# Quad_Board.net
KiCad netlist of a schematic drawn in EAGLE
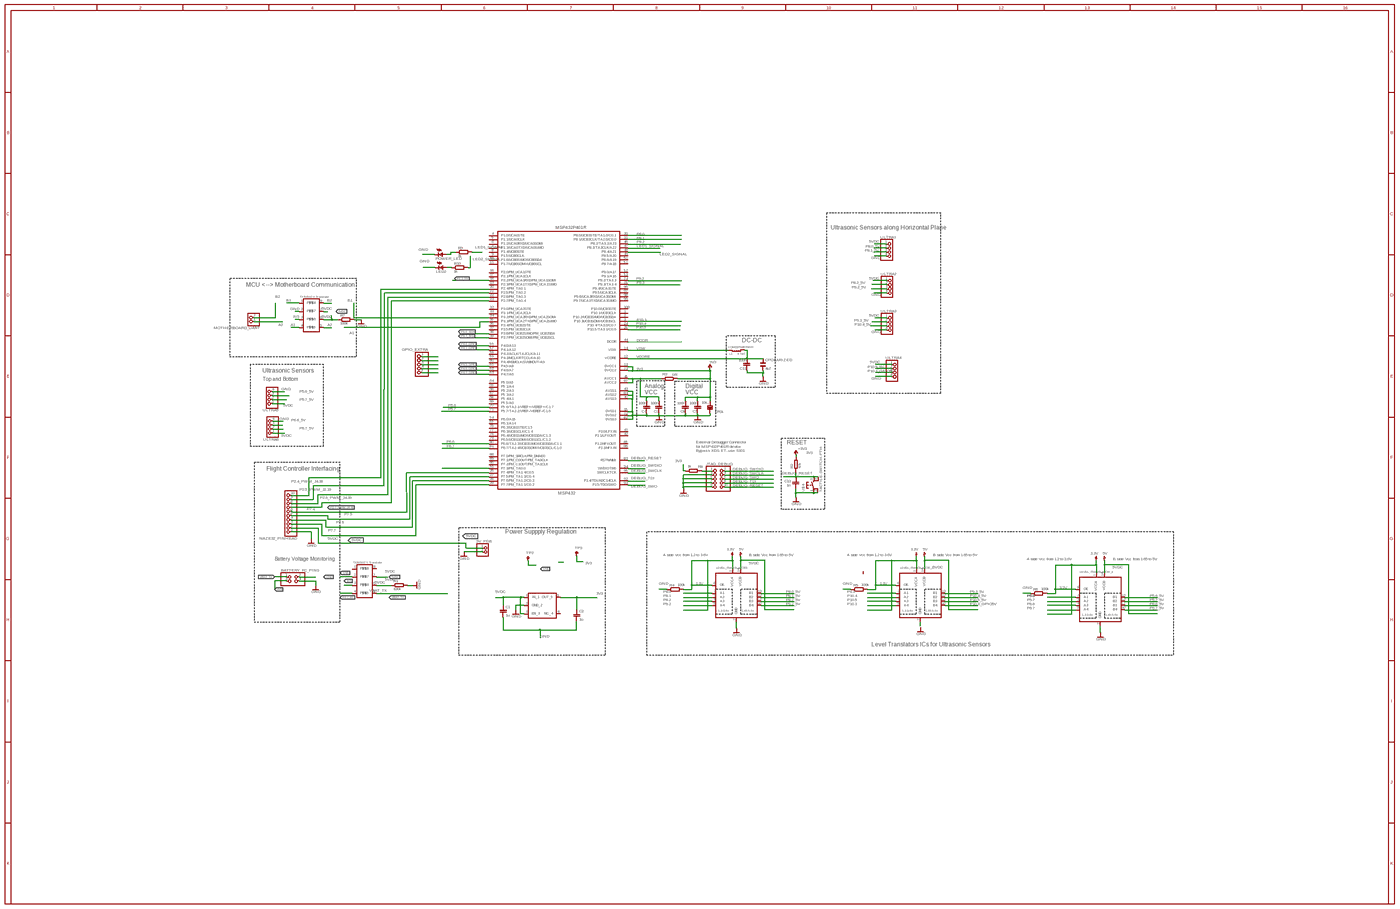
[diagram p0: schematic, sheet 1, overview]
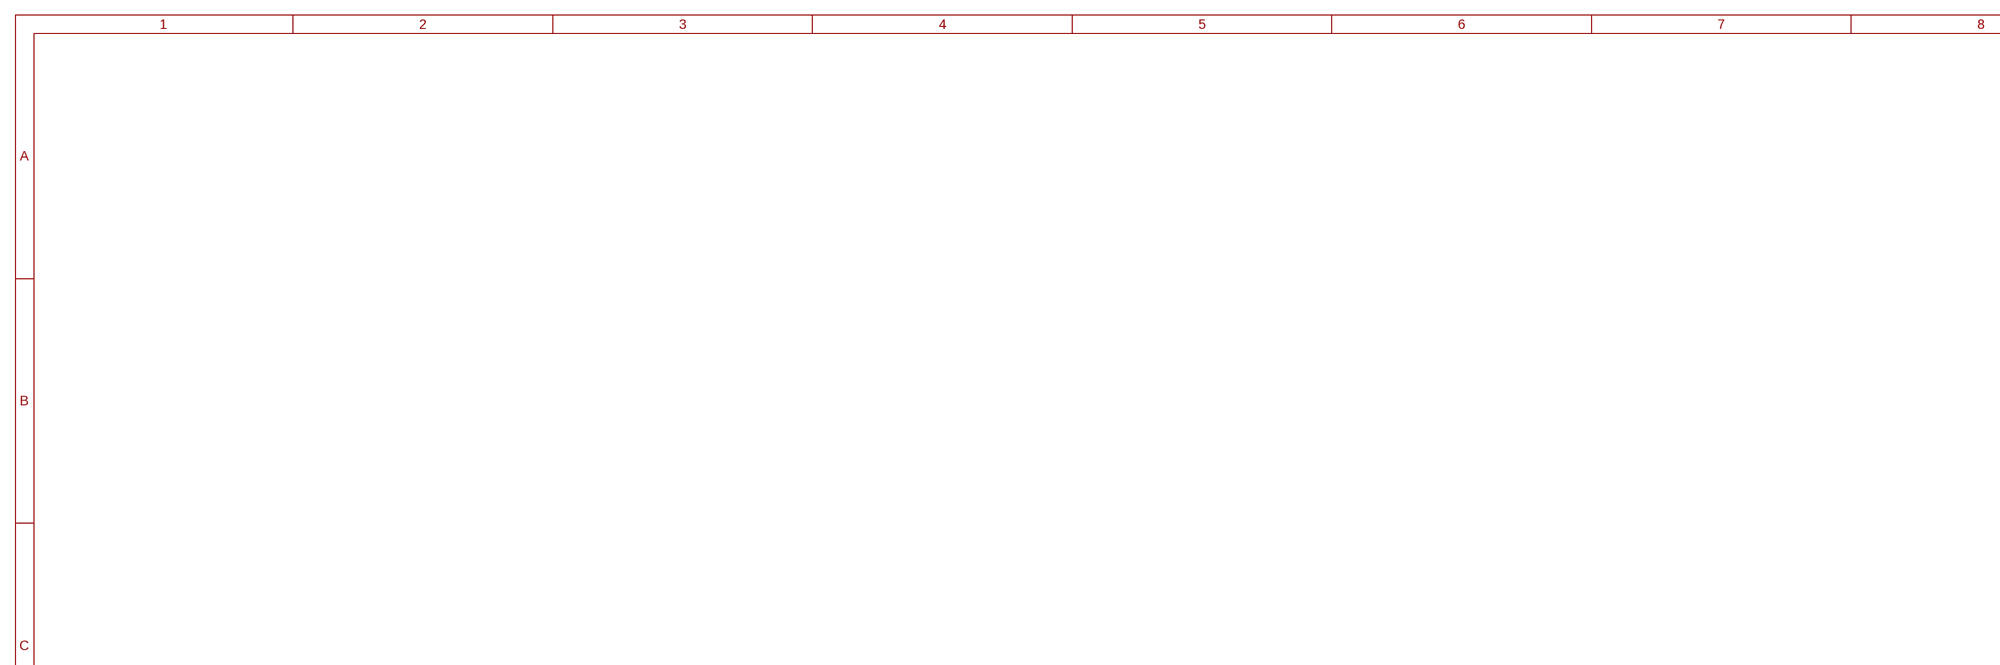
[diagram p1: schematic, sheet 1, part 1 of 4]
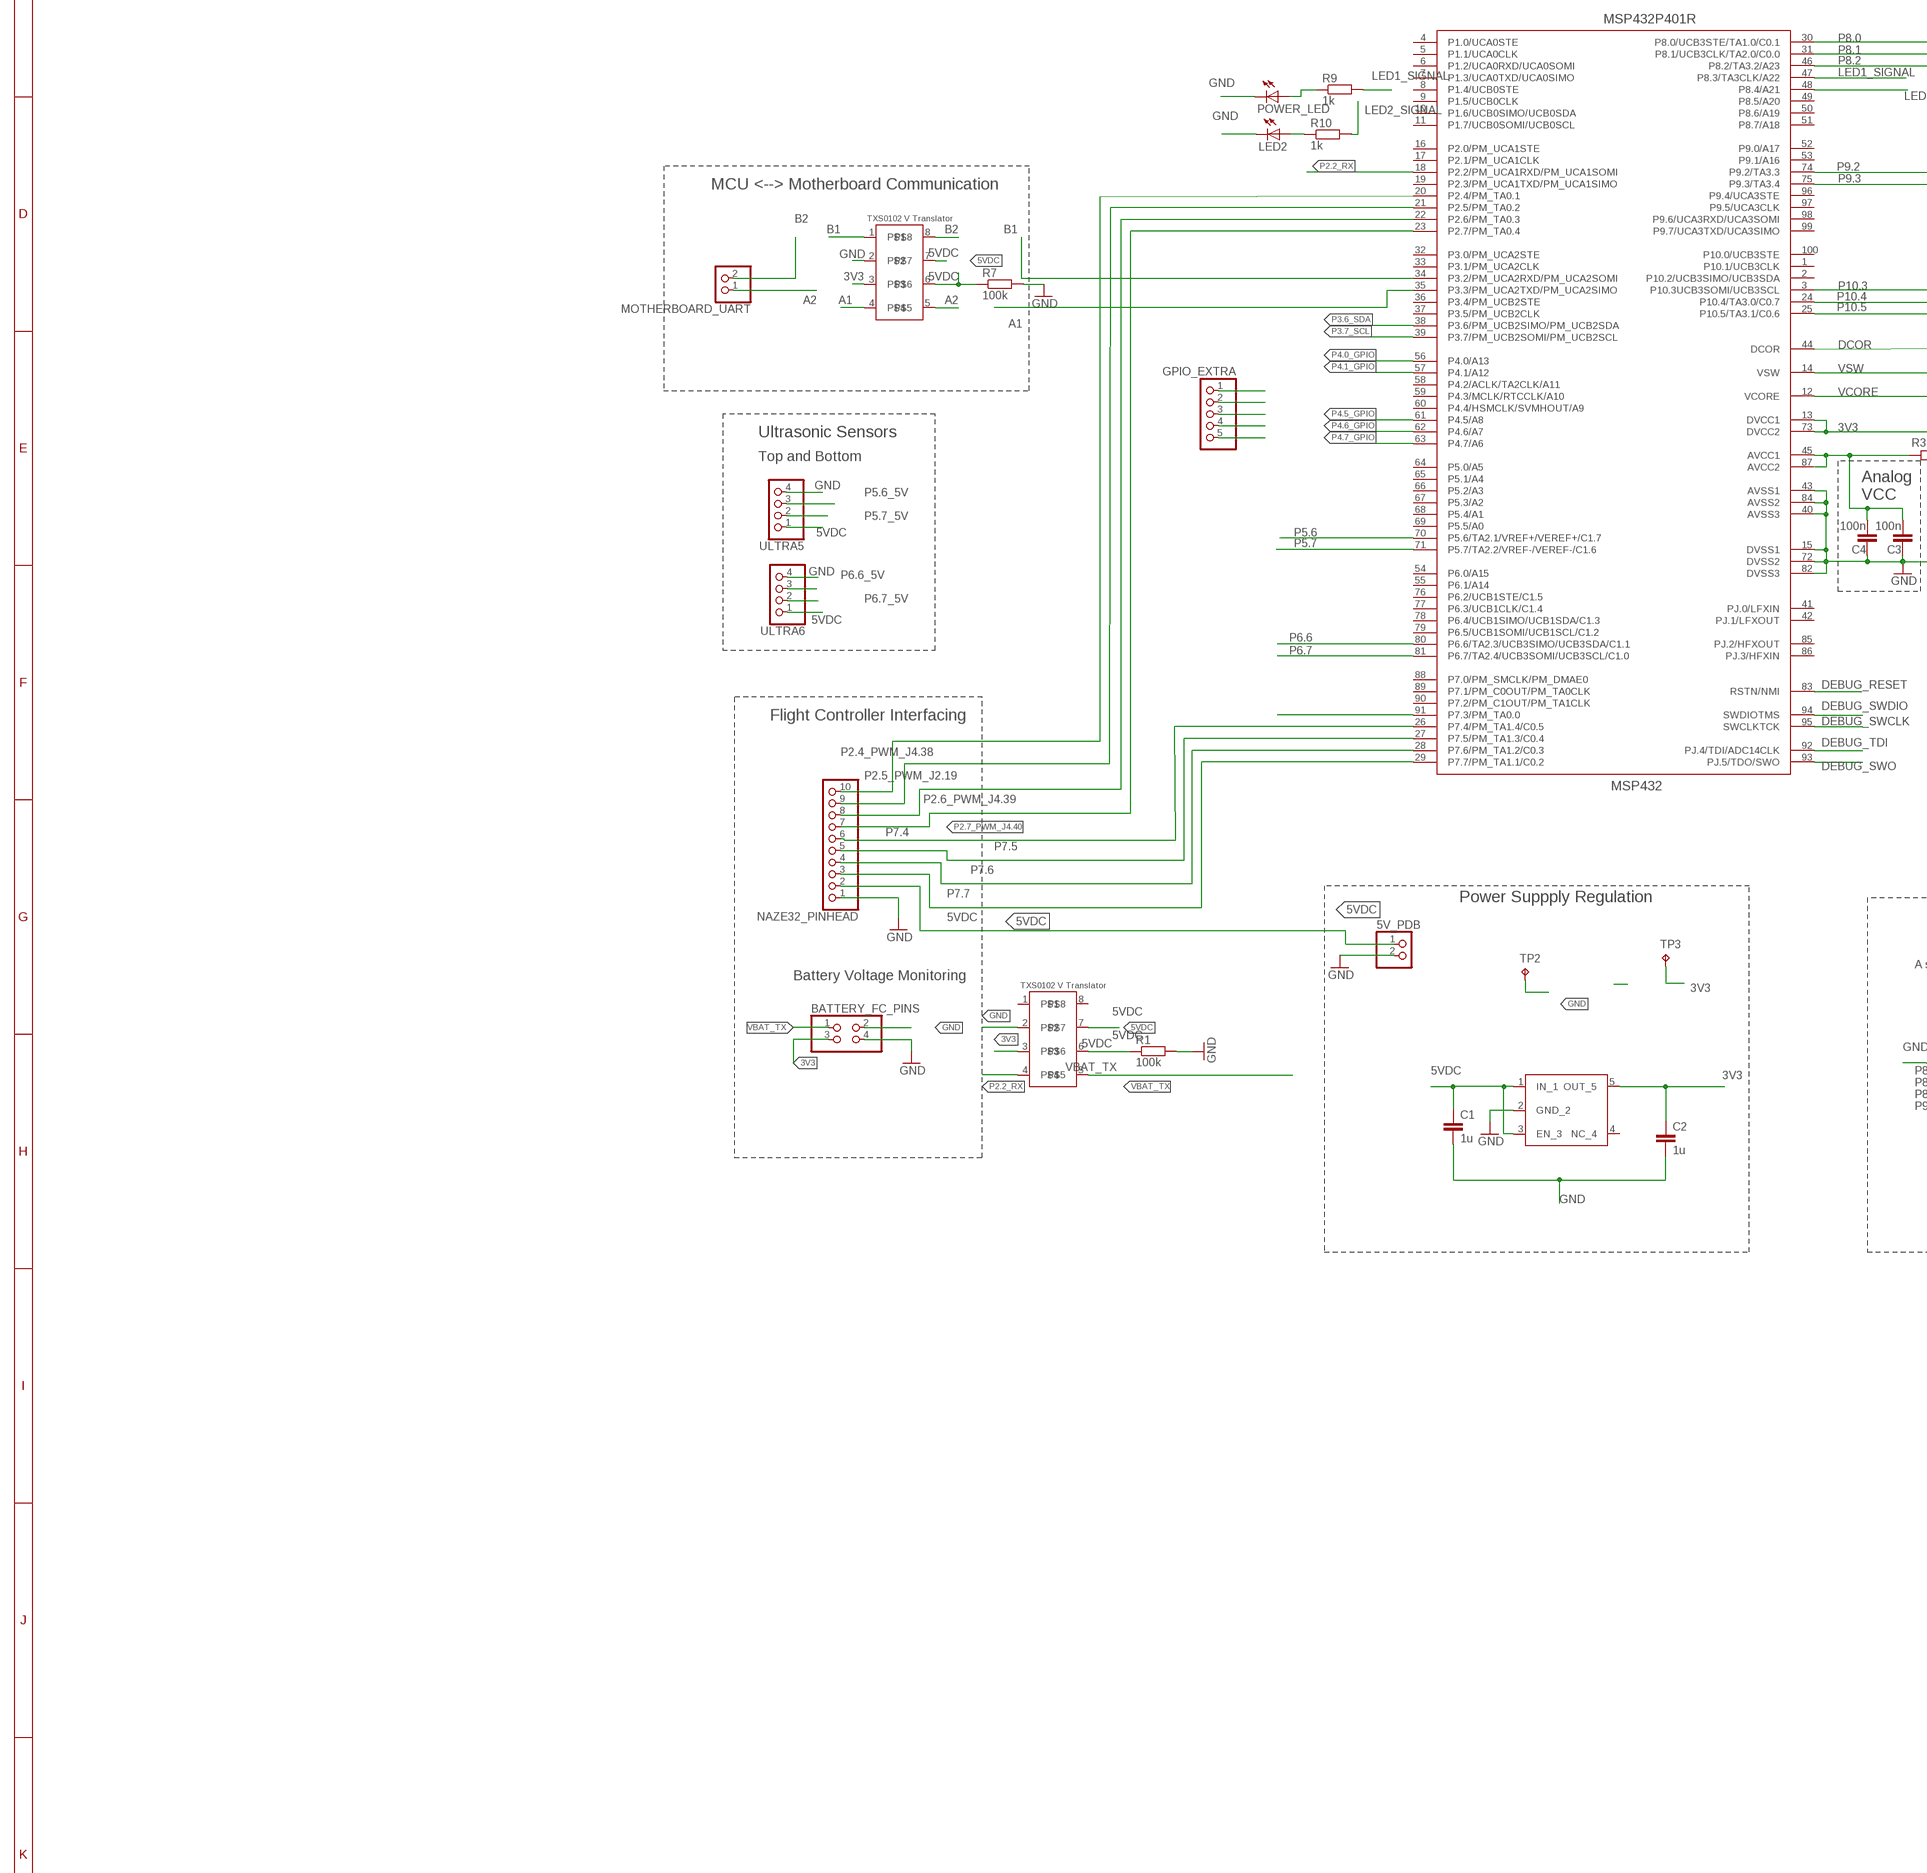
[diagram p2: schematic, sheet 1, part 2 of 4]
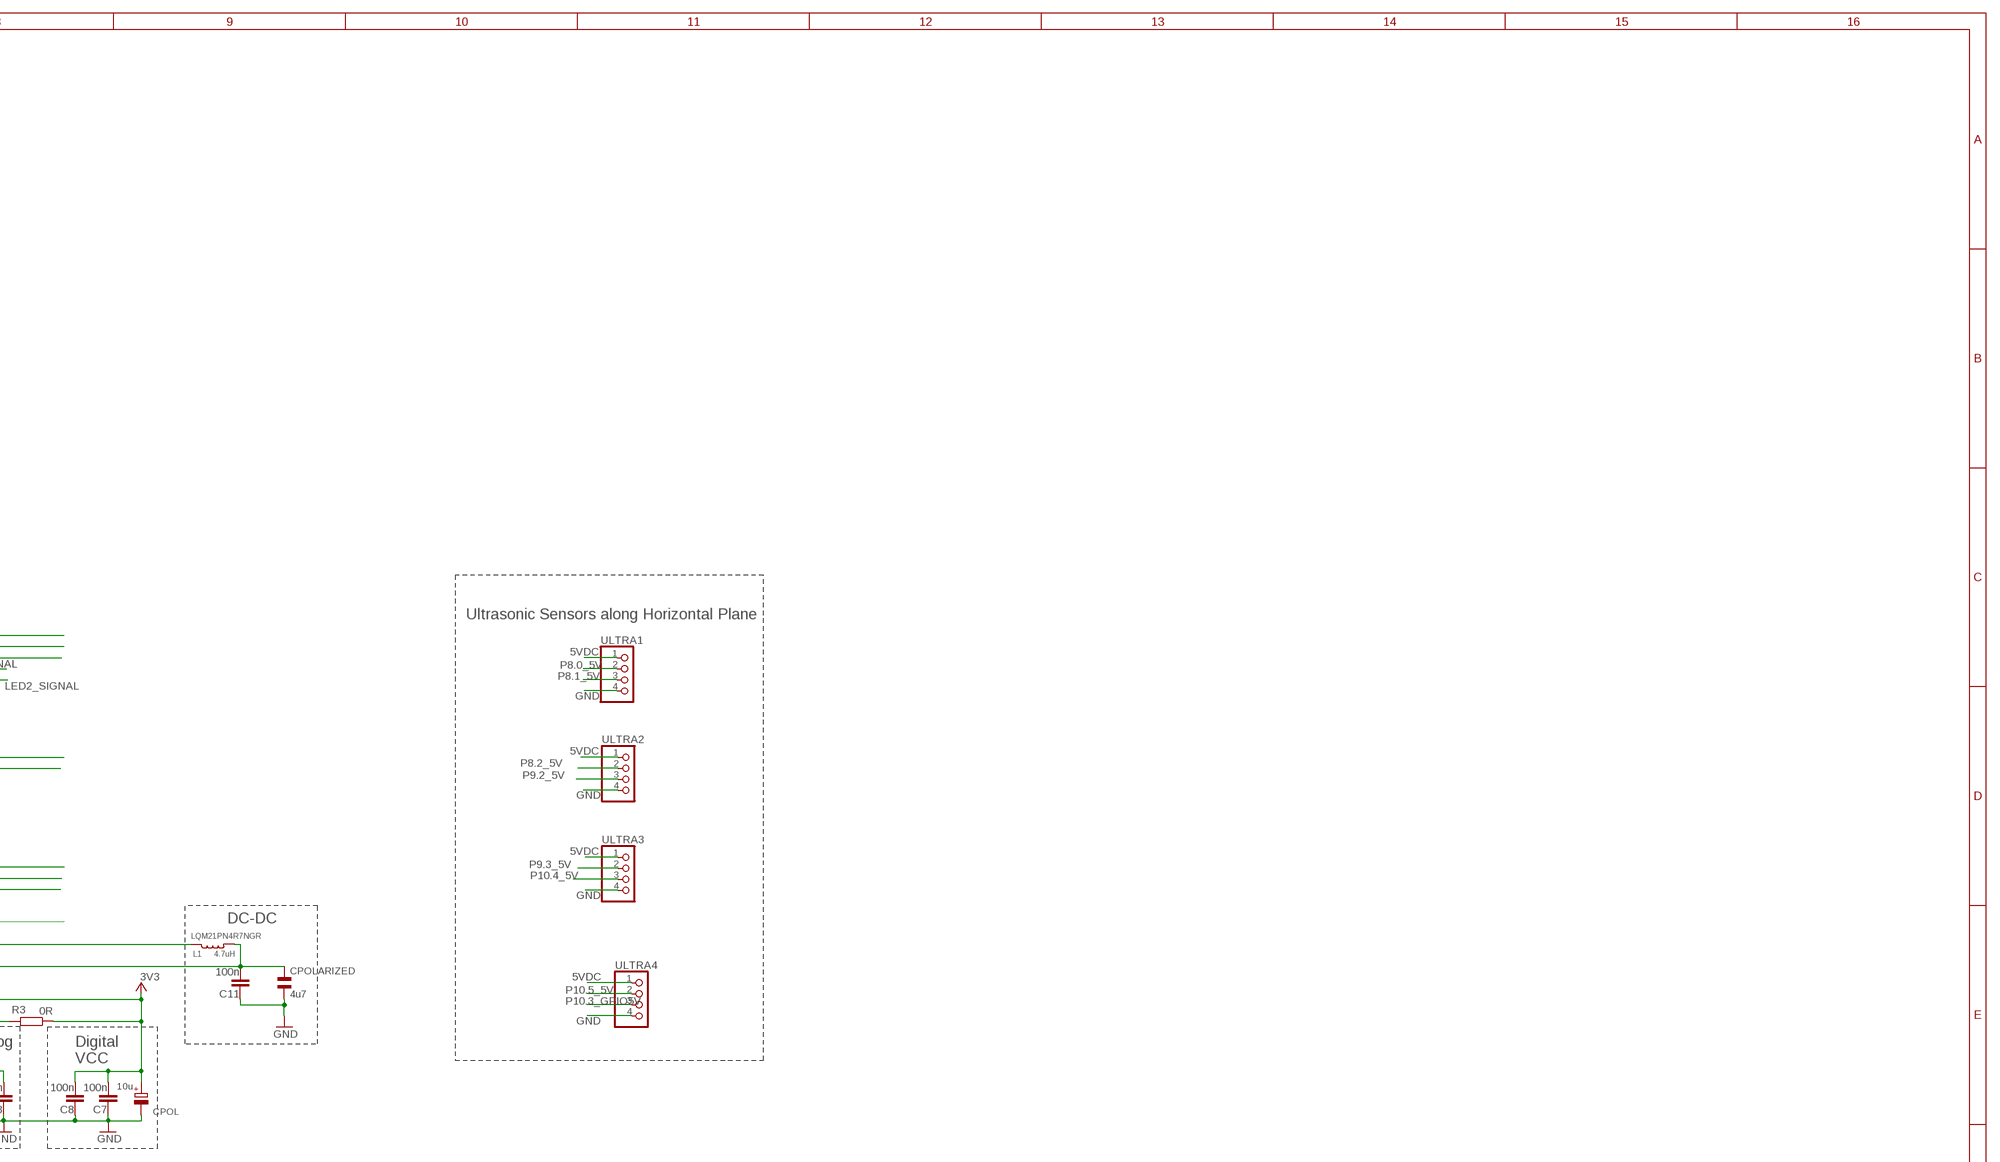
[diagram p3: schematic, sheet 1, part 3 of 4]
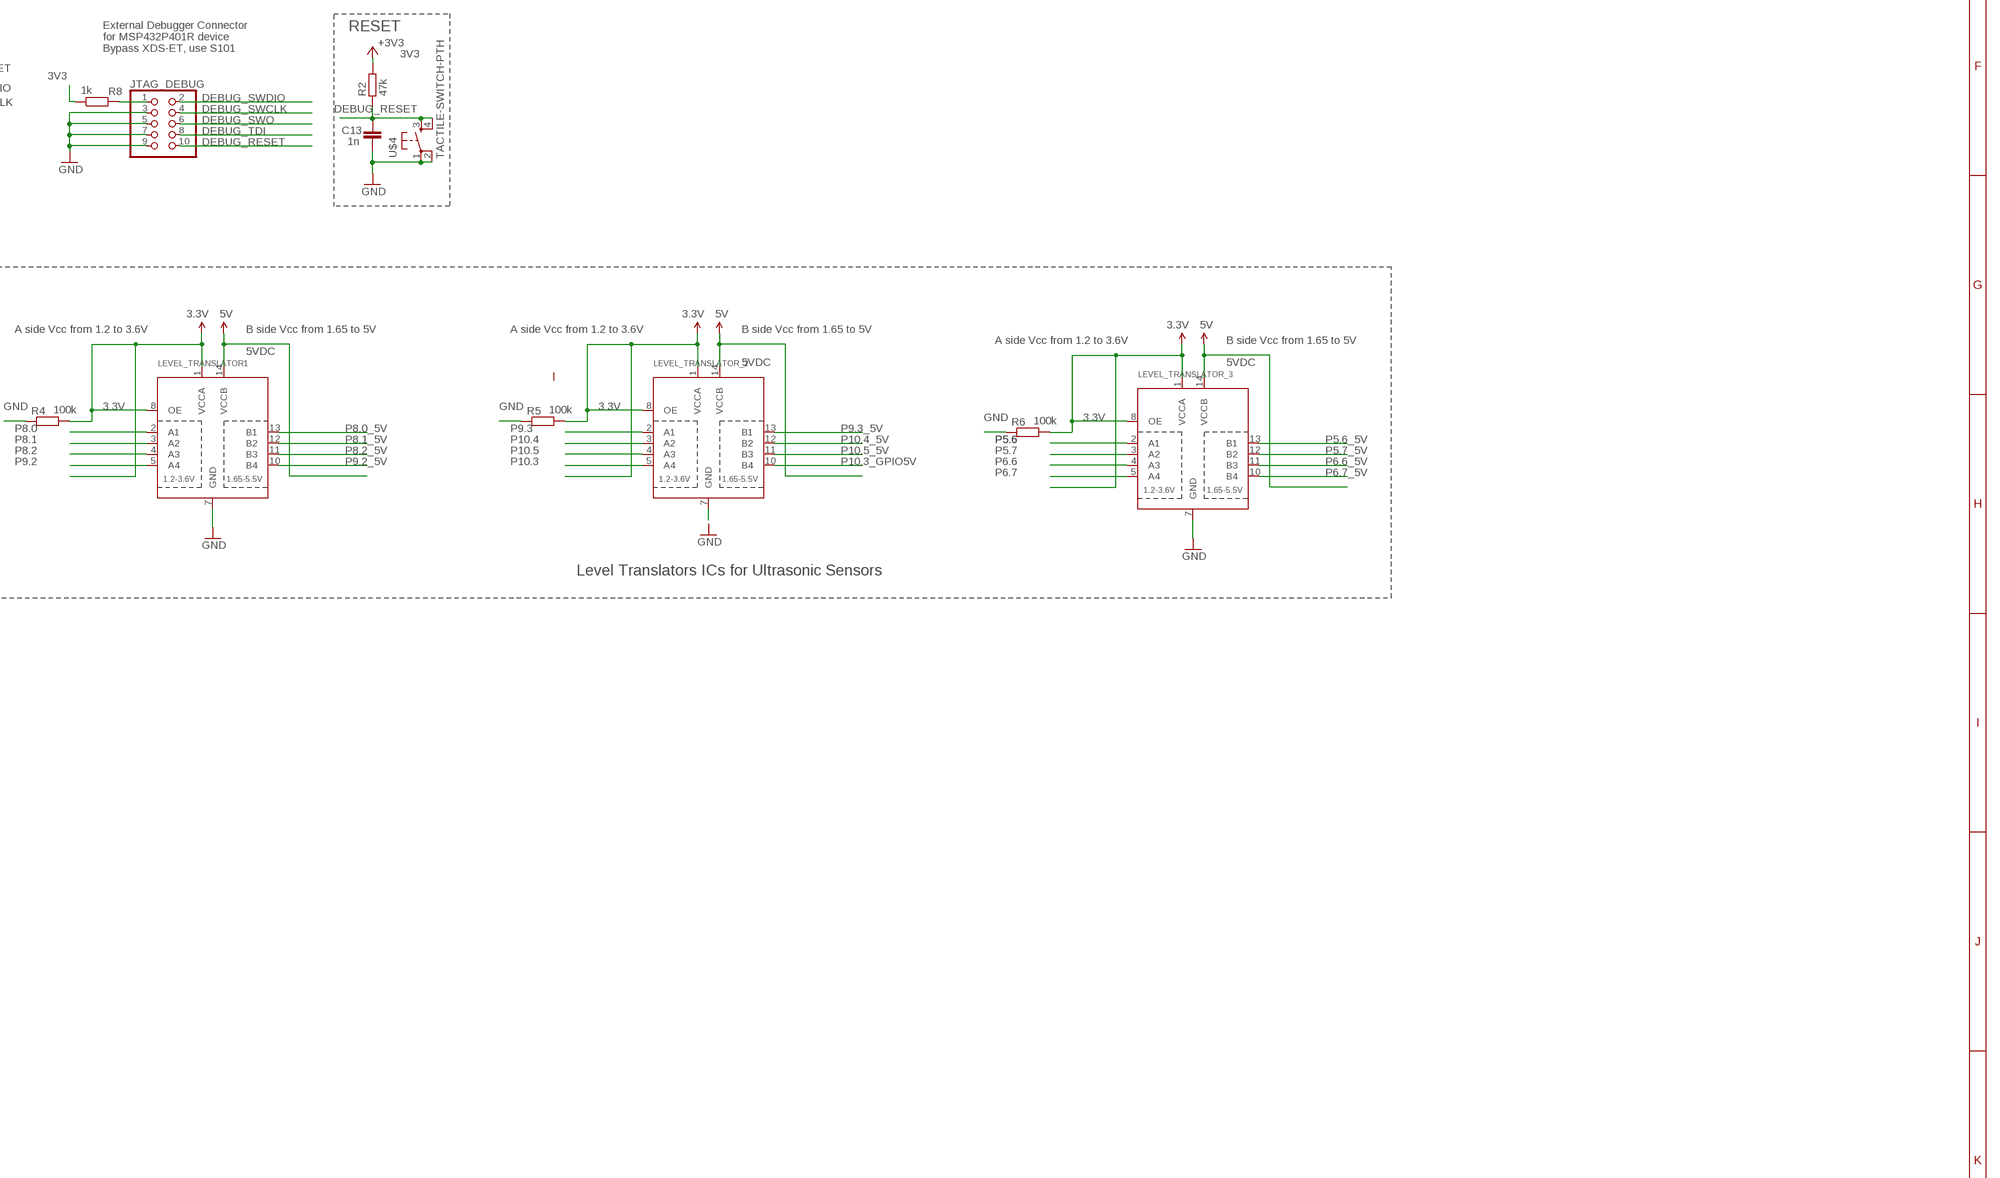
[diagram p4: schematic, sheet 1, part 4 of 4]

(export (version "E")
  (design (tool "Eeschema 10.0.6"))
  (components
    (comp (ref "5V_PDB")
      (value "PINHD-1X2")
      (footprint "eagle-import:1X02")
      (libsource (lib "eagle-import") (part "PINHD-1X2"))
    )
    (comp (ref "BATTERY_FC_PINS")
      (value "PINHD-2X2")
      (footprint "eagle-import:2X02")
      (libsource (lib "eagle-import") (part "PINHD-2X2"))
    )
    (comp (ref "C1")
      (value "1u")
      (footprint "eagle-import:C0805")
      (libsource (lib "eagle-import") (part "C-EUC0805"))
    )
    (comp (ref "C2")
      (value "1u")
      (footprint "eagle-import:C0805")
      (libsource (lib "eagle-import") (part "C-EUC0805"))
    )
    (comp (ref "C3")
      (value "100n")
      (footprint "eagle-import:C0805")
      (libsource (lib "eagle-import") (part "C-EUC0805"))
    )
    (comp (ref "C4")
      (value "100n")
      (footprint "eagle-import:C0805")
      (libsource (lib "eagle-import") (part "C-EUC0805"))
    )
    (comp (ref "C7")
      (value "100n")
      (footprint "eagle-import:C0805")
      (libsource (lib "eagle-import") (part "C-EUC0805"))
    )
    (comp (ref "C8")
      (value "100n")
      (footprint "eagle-import:C0805")
      (libsource (lib "eagle-import") (part "C-EUC0805"))
    )
    (comp (ref "C11")
      (value "100n")
      (footprint "eagle-import:C0805")
      (libsource (lib "eagle-import") (part "C-EUC0805"))
    )
    (comp (ref "C13")
      (value "1n")
      (footprint "eagle-import:C0805")
      (libsource (lib "eagle-import") (part "C-EUC0805"))
    )
    (comp (ref "CPOL")
      (value "10u")
      (footprint "eagle-import:A_3216-18R")
      (libsource (lib "eagle-import") (part "CPOL-EUA/3216-18R"))
    )
    (comp (ref "CPOLARIZED")
      (value "4u7")
      (footprint "eagle-import:CSMD0805")
      (libsource (lib "eagle-import") (part "CSMD0805"))
    )
    (comp (ref "GPIO_EXTRA")
      (value "PINHD-1X5")
      (footprint "eagle-import:1X05")
      (libsource (lib "eagle-import") (part "PINHD-1X5"))
    )
    (comp (ref "JTAG_DEBUG")
      (value "PINHD-2X5")
      (footprint "eagle-import:2X05")
      (libsource (lib "eagle-import") (part "PINHD-2X5"))
    )
    (comp (ref "L1")
      (value "4.7uH")
      (footprint "eagle-import:0806")
      (libsource (lib "eagle-import") (part "LQM2MP_G0"))
    )
    (comp (ref "LED2")
      (value "LED_E")
      (footprint "eagle-import:LED_1206")
      (libsource (lib "eagle-import") (part "LED_E"))
    )
    (comp (ref "LEVEL_TRANSLATOR1")
      (value "TXB0104PWRSOIC14")
      (footprint "eagle-import:SO14")
      (libsource (lib "eagle-import") (part "TXB0104PWRSOIC14"))
    )
    (comp (ref "LEVEL_TRANSLATOR_2")
      (value "TXB0104PWRSOIC14")
      (footprint "eagle-import:SO14")
      (libsource (lib "eagle-import") (part "TXB0104PWRSOIC14"))
    )
    (comp (ref "LEVEL_TRANSLATOR_3")
      (value "TXB0104PWRSOIC14")
      (footprint "eagle-import:SO14")
      (libsource (lib "eagle-import") (part "TXB0104PWRSOIC14"))
    )
    (comp (ref "MOTHERBOARD_UART")
      (value "PINHD-1X2")
      (footprint "eagle-import:1X02")
      (libsource (lib "eagle-import") (part "PINHD-1X2"))
    )
    (comp (ref "MSP432P401R")
      (value "MSP432")
      (footprint "eagle-import:PZ100")
      (libsource (lib "eagle-import") (part "MSP432"))
    )
    (comp (ref "NAZE32_PINHEAD")
      (value "PINHD-1X10")
      (footprint "eagle-import:1X10")
      (libsource (lib "eagle-import") (part "PINHD-1X10"))
    )
    (comp (ref "POWER_LED")
      (value "LED_E")
      (footprint "eagle-import:LED_1206")
      (libsource (lib "eagle-import") (part "LED_E"))
    )
    (comp (ref "R1")
      (value "100k")
      (footprint "eagle-import:M1206")
      (libsource (lib "eagle-import") (part "resistor_R-EU_M1206"))
    )
    (comp (ref "R2")
      (value "47k")
      (footprint "eagle-import:R1206")
      (libsource (lib "eagle-import") (part "R-EU_R1206"))
    )
    (comp (ref "R3")
      (value "0R")
      (footprint "eagle-import:0402")
      (libsource (lib "eagle-import") (part "R-EU_RM0402"))
    )
    (comp (ref "R4")
      (value "100k")
      (footprint "eagle-import:M1206")
      (libsource (lib "eagle-import") (part "resistor_R-EU_M1206"))
    )
    (comp (ref "R5")
      (value "100k")
      (footprint "eagle-import:M1206")
      (libsource (lib "eagle-import") (part "resistor_R-EU_M1206"))
    )
    (comp (ref "R6")
      (value "100k")
      (footprint "eagle-import:M1206")
      (libsource (lib "eagle-import") (part "resistor_R-EU_M1206"))
    )
    (comp (ref "R7")
      (value "100k")
      (footprint "eagle-import:M1206")
      (libsource (lib "eagle-import") (part "resistor_R-EU_M1206"))
    )
    (comp (ref "R8")
      (value "1k")
      (footprint "eagle-import:R1206")
      (libsource (lib "eagle-import") (part "R-EU_R1206"))
    )
    (comp (ref "R9")
      (value "1k")
      (footprint "eagle-import:M0805")
      (libsource (lib "eagle-import") (part "resistor_R-EU_M0805"))
    )
    (comp (ref "R10")
      (value "1k")
      (footprint "eagle-import:M0805")
      (libsource (lib "eagle-import") (part "resistor_R-EU_M0805"))
    )
    (comp (ref "TP2")
      (value "TPB2,54")
      (footprint "eagle-import:B2,54")
      (libsource (lib "eagle-import") (part "TPB2,54"))
    )
    (comp (ref "TP3")
      (value "TPB2,54")
      (footprint "eagle-import:B2,54")
      (libsource (lib "eagle-import") (part "TPB2,54"))
    )
    (comp (ref "U$1")
      (value "TXS0102")
      (footprint "eagle-import:DCT_R-PDSO-G8")
      (libsource (lib "eagle-import") (part "TXS0102"))
    )
    (comp (ref "U$2")
      (value "TLV733P")
      (footprint "eagle-import:SOT23-5")
      (libsource (lib "eagle-import") (part "TLV733P"))
    )
    (comp (ref "U$3")
      (value "TXS0102")
      (footprint "eagle-import:DCT_R-PDSO-G8")
      (libsource (lib "eagle-import") (part "TXS0102"))
    )
    (comp (ref "U$4")
      (value "TACTILE-SWITCH-PTH")
      (footprint "eagle-import:TAC-SWITCH-PTH")
      (libsource (lib "eagle-import") (part "TACTILE-SWITCH-PTH"))
    )
    (comp (ref "ULTRA1")
      (value "PINHD-1X4")
      (footprint "eagle-import:1X04")
      (libsource (lib "eagle-import") (part "PINHD-1X4"))
    )
    (comp (ref "ULTRA2")
      (value "PINHD-1X4")
      (footprint "eagle-import:1X04")
      (libsource (lib "eagle-import") (part "PINHD-1X4"))
    )
    (comp (ref "ULTRA3")
      (value "PINHD-1X4")
      (footprint "eagle-import:1X04")
      (libsource (lib "eagle-import") (part "PINHD-1X4"))
    )
    (comp (ref "ULTRA4")
      (value "PINHD-1X4")
      (footprint "eagle-import:1X04")
      (libsource (lib "eagle-import") (part "PINHD-1X4"))
    )
    (comp (ref "ULTRA5")
      (value "PINHD-1X4")
      (footprint "eagle-import:1X04")
      (libsource (lib "eagle-import") (part "PINHD-1X4"))
    )
    (comp (ref "ULTRA6")
      (value "PINHD-1X4")
      (footprint "eagle-import:1X04")
      (libsource (lib "eagle-import") (part "PINHD-1X4"))
    )
  )
  (nets
    (net (code "1") (name "/A1") (class "Default")
      (node (ref "MSP432P401R") (pin "35") (pinfunction "P3.3/PM_UCA2TXD/PM_UCA2SIMO_35") (pintype "power_in"))
      (node (ref "U$1") (pin "4") (pinfunction "P$4_4") (pintype "bidirectional"))
    )
    (net (code "2") (name "/A2") (class "Default")
      (node (ref "MOTHERBOARD_UART") (pin "1") (pinfunction "1_1") (pintype "passive"))
      (node (ref "U$1") (pin "5") (pinfunction "P$5_5") (pintype "bidirectional"))
    )
    (net (code "3") (name "/B1") (class "Default")
      (node (ref "MSP432P401R") (pin "34") (pinfunction "P3.2/PM_UCA2RXD/PM_UCA2SOMI_34") (pintype "power_in"))
      (node (ref "U$1") (pin "1") (pinfunction "P$1_1") (pintype "bidirectional"))
    )
    (net (code "4") (name "/B2") (class "Default")
      (node (ref "MOTHERBOARD_UART") (pin "2") (pinfunction "2_2") (pintype "passive"))
      (node (ref "U$1") (pin "8") (pinfunction "P$8_8") (pintype "bidirectional"))
    )
    (net (code "5") (name "/DCOR") (class "Default")
      (node (ref "MSP432P401R") (pin "44") (pinfunction "DCOR_44") (pintype "power_in"))
    )
    (net (code "6") (name "/DEBUG_RESET") (class "Default")
      (node (ref "C13") (pin "1") (pinfunction "1_1") (pintype "passive"))
      (node (ref "JTAG_DEBUG") (pin "10") (pinfunction "10_10") (pintype "passive"))
      (node (ref "MSP432P401R") (pin "83") (pinfunction "RSTN/NMI_83") (pintype "power_in"))
      (node (ref "R2") (pin "1") (pinfunction "1_1") (pintype "passive"))
      (node (ref "U$4") (pin "3") (pinfunction "3_3") (pintype "passive"))
      (node (ref "U$4") (pin "4") (pinfunction "4_4") (pintype "passive"))
    )
    (net (code "7") (name "/DEBUG_SWCLK") (class "Default")
      (node (ref "JTAG_DEBUG") (pin "4") (pinfunction "4_4") (pintype "passive"))
      (node (ref "MSP432P401R") (pin "95") (pinfunction "SWCLKTCK_95") (pintype "power_in"))
    )
    (net (code "8") (name "/DEBUG_SWDIO") (class "Default")
      (node (ref "JTAG_DEBUG") (pin "2") (pinfunction "2_2") (pintype "passive"))
      (node (ref "MSP432P401R") (pin "94") (pinfunction "SWDIOTMS_94") (pintype "power_in"))
    )
    (net (code "9") (name "/DEBUG_SWO") (class "Default")
      (node (ref "JTAG_DEBUG") (pin "6") (pinfunction "6_6") (pintype "passive"))
      (node (ref "MSP432P401R") (pin "93") (pinfunction "PJ.5/TDO/SWO_93") (pintype "power_in"))
    )
    (net (code "10") (name "/DEBUG_TDI") (class "Default")
      (node (ref "JTAG_DEBUG") (pin "8") (pinfunction "8_8") (pintype "passive"))
      (node (ref "MSP432P401R") (pin "92") (pinfunction "PJ.4/TDI/ADC14CLK_92") (pintype "power_in"))
    )
    (net (code "11") (name "/LED1_SIGNAL") (class "Default")
      (node (ref "MSP432P401R") (pin "47") (pinfunction "P8.3/TA3CLK/A22_47") (pintype "power_in"))
      (node (ref "R9") (pin "2") (pinfunction "2_2") (pintype "passive"))
    )
    (net (code "12") (name "/LED2_SIGNAL") (class "Default")
      (node (ref "MSP432P401R") (pin "48") (pinfunction "P8.4/A21_48") (pintype "power_in"))
      (node (ref "R10") (pin "2") (pinfunction "2_2") (pintype "passive"))
    )
    (net (code "13") (name "/P1.0{slash}UCA0STE") (class "Default")
      (node (ref "MSP432P401R") (pin "4") (pinfunction "P1.0/UCA0STE_4") (pintype "power_in"))
    )
    (net (code "14") (name "/P1.1{slash}UCA0CLK") (class "Default")
      (node (ref "MSP432P401R") (pin "5") (pinfunction "P1.1/UCA0CLK_5") (pintype "power_in"))
    )
    (net (code "15") (name "/P1.2{slash}UCA0RXD{slash}UCA0SOMI") (class "Default")
      (node (ref "MSP432P401R") (pin "6") (pinfunction "P1.2/UCA0RXD/UCA0SOMI_6") (pintype "power_in"))
    )
    (net (code "16") (name "/P1.3{slash}UCA0TXD{slash}UCA0SIMO") (class "Default")
      (node (ref "MSP432P401R") (pin "7") (pinfunction "P1.3/UCA0TXD/UCA0SIMO_7") (pintype "power_in"))
    )
    (net (code "17") (name "/P1.4{slash}UCB0STE") (class "Default")
      (node (ref "MSP432P401R") (pin "8") (pinfunction "P1.4/UCB0STE_8") (pintype "power_in"))
    )
    (net (code "18") (name "/P1.5{slash}UCB0CLK") (class "Default")
      (node (ref "MSP432P401R") (pin "9") (pinfunction "P1.5/UCB0CLK_9") (pintype "power_in"))
    )
    (net (code "19") (name "/P1.6{slash}UCB0SIMO{slash}UCB0SDA") (class "Default")
      (node (ref "MSP432P401R") (pin "10") (pinfunction "P1.6/UCB0SIMO/UCB0SDA_10") (pintype "power_in"))
    )
    (net (code "20") (name "/P1.7{slash}UCB0SOMI{slash}UCB0SCL") (class "Default")
      (node (ref "MSP432P401R") (pin "11") (pinfunction "P1.7/UCB0SOMI/UCB0SCL_11") (pintype "power_in"))
    )
    (net (code "21") (name "/P2.0{slash}PM_UCA1STE") (class "Default")
      (node (ref "MSP432P401R") (pin "16") (pinfunction "P2.0/PM_UCA1STE_16") (pintype "power_in"))
    )
    (net (code "22") (name "/P2.1{slash}PM_UCA1CLK") (class "Default")
      (node (ref "MSP432P401R") (pin "17") (pinfunction "P2.1/PM_UCA1CLK_17") (pintype "power_in"))
    )
    (net (code "23") (name "/P2.3{slash}PM_UCA1TXD{slash}PM_UCA1SIMO") (class "Default")
      (node (ref "MSP432P401R") (pin "19") (pinfunction "P2.3/PM_UCA1TXD/PM_UCA1SIMO_19") (pintype "power_in"))
    )
    (net (code "24") (name "/P2.4_PWM_J4.38") (class "Default")
      (node (ref "MSP432P401R") (pin "20") (pinfunction "P2.4/PM_TA0.1_20") (pintype "power_in"))
      (node (ref "NAZE32_PINHEAD") (pin "10") (pinfunction "10_10") (pintype "passive"))
    )
    (net (code "25") (name "/P2.5_PWM_J2.19") (class "Default")
      (node (ref "MSP432P401R") (pin "21") (pinfunction "P2.5/PM_TA0.2_21") (pintype "power_in"))
      (node (ref "NAZE32_PINHEAD") (pin "9") (pinfunction "9_9") (pintype "passive"))
    )
    (net (code "26") (name "/P2.6_PWM_J4.39") (class "Default")
      (node (ref "MSP432P401R") (pin "22") (pinfunction "P2.6/PM_TA0.3_22") (pintype "power_in"))
      (node (ref "NAZE32_PINHEAD") (pin "8") (pinfunction "8_8") (pintype "passive"))
    )
    (net (code "27") (name "/P3.0{slash}PM_UCA2STE") (class "Default")
      (node (ref "MSP432P401R") (pin "32") (pinfunction "P3.0/PM_UCA2STE_32") (pintype "power_in"))
    )
    (net (code "28") (name "/P3.1{slash}PM_UCA2CLK") (class "Default")
      (node (ref "MSP432P401R") (pin "33") (pinfunction "P3.1/PM_UCA2CLK_33") (pintype "power_in"))
    )
    (net (code "29") (name "/P3.4{slash}PM_UCB2STE") (class "Default")
      (node (ref "MSP432P401R") (pin "36") (pinfunction "P3.4/PM_UCB2STE_36") (pintype "power_in"))
    )
    (net (code "30") (name "/P3.5{slash}PM_UCB2CLK") (class "Default")
      (node (ref "MSP432P401R") (pin "37") (pinfunction "P3.5/PM_UCB2CLK_37") (pintype "power_in"))
    )
    (net (code "31") (name "/P4.2{slash}ACLK{slash}TA2CLK{slash}A11") (class "Default")
      (node (ref "MSP432P401R") (pin "58") (pinfunction "P4.2/ACLK/TA2CLK/A11_58") (pintype "power_in"))
    )
    (net (code "32") (name "/P4.3{slash}MCLK{slash}RTCCLK{slash}A10") (class "Default")
      (node (ref "MSP432P401R") (pin "59") (pinfunction "P4.3/MCLK/RTCCLK/A10_59") (pintype "power_in"))
    )
    (net (code "33") (name "/P4.4{slash}HSMCLK{slash}SVMHOUT{slash}A9") (class "Default")
      (node (ref "MSP432P401R") (pin "60") (pinfunction "P4.4/HSMCLK/SVMHOUT/A9_60") (pintype "power_in"))
    )
    (net (code "34") (name "/P5.0{slash}A5") (class "Default")
      (node (ref "MSP432P401R") (pin "64") (pinfunction "P5.0/A5_64") (pintype "power_in"))
    )
    (net (code "35") (name "/P5.1{slash}A4") (class "Default")
      (node (ref "MSP432P401R") (pin "65") (pinfunction "P5.1/A4_65") (pintype "power_in"))
    )
    (net (code "36") (name "/P5.2{slash}A3") (class "Default")
      (node (ref "MSP432P401R") (pin "66") (pinfunction "P5.2/A3_66") (pintype "power_in"))
    )
    (net (code "37") (name "/P5.3{slash}A2") (class "Default")
      (node (ref "MSP432P401R") (pin "67") (pinfunction "P5.3/A2_67") (pintype "power_in"))
    )
    (net (code "38") (name "/P5.4{slash}A1") (class "Default")
      (node (ref "MSP432P401R") (pin "68") (pinfunction "P5.4/A1_68") (pintype "power_in"))
    )
    (net (code "39") (name "/P5.5{slash}A0") (class "Default")
      (node (ref "MSP432P401R") (pin "69") (pinfunction "P5.5/A0_69") (pintype "power_in"))
    )
    (net (code "40") (name "/P5.6") (class "Default")
      (node (ref "LEVEL_TRANSLATOR_3") (pin "2") (pinfunction "A1_2") (pintype "bidirectional"))
      (node (ref "MSP432P401R") (pin "70") (pinfunction "P5.6/TA2.1/VREF+/VEREF+/C1.7_70") (pintype "power_in"))
    )
    (net (code "41") (name "/P5.6_5V") (class "Default")
      (node (ref "LEVEL_TRANSLATOR_3") (pin "13") (pinfunction "B1_13") (pintype "bidirectional"))
      (node (ref "ULTRA5") (pin "3") (pinfunction "3_3") (pintype "passive"))
    )
    (net (code "42") (name "/P5.7") (class "Default")
      (node (ref "LEVEL_TRANSLATOR_3") (pin "3") (pinfunction "A2_3") (pintype "bidirectional"))
      (node (ref "MSP432P401R") (pin "71") (pinfunction "P5.7/TA2.2/VREF-/VEREF-/C1.6_71") (pintype "power_in"))
    )
    (net (code "43") (name "/P5.7_5V") (class "Default")
      (node (ref "LEVEL_TRANSLATOR_3") (pin "12") (pinfunction "B2_12") (pintype "bidirectional"))
      (node (ref "ULTRA5") (pin "2") (pinfunction "2_2") (pintype "passive"))
    )
    (net (code "44") (name "/P6.0{slash}A15") (class "Default")
      (node (ref "MSP432P401R") (pin "54") (pinfunction "P6.0/A15_54") (pintype "power_in"))
    )
    (net (code "45") (name "/P6.1{slash}A14") (class "Default")
      (node (ref "MSP432P401R") (pin "55") (pinfunction "P6.1/A14_55") (pintype "power_in"))
    )
    (net (code "46") (name "/P6.2{slash}UCB1STE{slash}C1.5") (class "Default")
      (node (ref "MSP432P401R") (pin "76") (pinfunction "P6.2/UCB1STE/C1.5_76") (pintype "power_in"))
    )
    (net (code "47") (name "/P6.3{slash}UCB1CLK{slash}C1.4") (class "Default")
      (node (ref "MSP432P401R") (pin "77") (pinfunction "P6.3/UCB1CLK/C1.4_77") (pintype "power_in"))
    )
    (net (code "48") (name "/P6.4{slash}UCB1SIMO{slash}UCB1SDA{slash}C1.3") (class "Default")
      (node (ref "MSP432P401R") (pin "78") (pinfunction "P6.4/UCB1SIMO/UCB1SDA/C1.3_78") (pintype "power_in"))
    )
    (net (code "49") (name "/P6.5{slash}UCB1SOMI{slash}UCB1SCL{slash}C1.2") (class "Default")
      (node (ref "MSP432P401R") (pin "79") (pinfunction "P6.5/UCB1SOMI/UCB1SCL/C1.2_79") (pintype "power_in"))
    )
    (net (code "50") (name "/P6.6") (class "Default")
      (node (ref "LEVEL_TRANSLATOR_3") (pin "4") (pinfunction "A3_4") (pintype "bidirectional"))
      (node (ref "MSP432P401R") (pin "80") (pinfunction "P6.6/TA2.3/UCB3SIMO/UCB3SDA/C1.1_80") (pintype "power_in"))
    )
    (net (code "51") (name "/P6.6_5V") (class "Default")
      (node (ref "LEVEL_TRANSLATOR_3") (pin "11") (pinfunction "B3_11") (pintype "bidirectional"))
      (node (ref "ULTRA6") (pin "3") (pinfunction "3_3") (pintype "passive"))
    )
    (net (code "52") (name "/P6.7") (class "Default")
      (node (ref "LEVEL_TRANSLATOR_3") (pin "5") (pinfunction "A4_5") (pintype "bidirectional"))
      (node (ref "MSP432P401R") (pin "81") (pinfunction "P6.7/TA2.4/UCB3SOMI/UCB3SCL/C1.0_81") (pintype "power_in"))
    )
    (net (code "53") (name "/P6.7_5V") (class "Default")
      (node (ref "LEVEL_TRANSLATOR_3") (pin "10") (pinfunction "B4_10") (pintype "bidirectional"))
      (node (ref "ULTRA6") (pin "2") (pinfunction "2_2") (pintype "passive"))
    )
    (net (code "54") (name "/P7.0{slash}PM_SMCLK{slash}PM_DMAE0") (class "Default")
      (node (ref "MSP432P401R") (pin "88") (pinfunction "P7.0/PM_SMCLK/PM_DMAE0_88") (pintype "power_in"))
    )
    (net (code "55") (name "/P7.1{slash}PM_C0OUT{slash}PM_TA0CLK") (class "Default")
      (node (ref "MSP432P401R") (pin "89") (pinfunction "P7.1/PM_C0OUT/PM_TA0CLK_89") (pintype "power_in"))
    )
    (net (code "56") (name "/P7.2{slash}PM_C1OUT{slash}PM_TA1CLK") (class "Default")
      (node (ref "MSP432P401R") (pin "90") (pinfunction "P7.2/PM_C1OUT/PM_TA1CLK_90") (pintype "power_in"))
    )
    (net (code "57") (name "/P7.4") (class "Default")
      (node (ref "MSP432P401R") (pin "26") (pinfunction "P7.4/PM_TA1.4/C0.5_26") (pintype "power_in"))
      (node (ref "NAZE32_PINHEAD") (pin "6") (pinfunction "6_6") (pintype "passive"))
    )
    (net (code "58") (name "/P7.5") (class "Default")
      (node (ref "MSP432P401R") (pin "27") (pinfunction "P7.5/PM_TA1.3/C0.4_27") (pintype "power_in"))
      (node (ref "NAZE32_PINHEAD") (pin "5") (pinfunction "5_5") (pintype "passive"))
    )
    (net (code "59") (name "/P7.6") (class "Default")
      (node (ref "MSP432P401R") (pin "28") (pinfunction "P7.6/PM_TA1.2/C0.3_28") (pintype "power_in"))
      (node (ref "NAZE32_PINHEAD") (pin "4") (pinfunction "4_4") (pintype "passive"))
    )
    (net (code "60") (name "/P7.7") (class "Default")
      (node (ref "MSP432P401R") (pin "29") (pinfunction "P7.7/PM_TA1.1/C0.2_29") (pintype "power_in"))
      (node (ref "NAZE32_PINHEAD") (pin "3") (pinfunction "3_3") (pintype "passive"))
    )
    (net (code "61") (name "/P8.0") (class "Default")
      (node (ref "LEVEL_TRANSLATOR1") (pin "2") (pinfunction "A1_2") (pintype "bidirectional"))
      (node (ref "MSP432P401R") (pin "30") (pinfunction "P8.0/UCB3STE/TA1.0/C0.1_30") (pintype "power_in"))
    )
    (net (code "62") (name "/P8.0_5V") (class "Default")
      (node (ref "LEVEL_TRANSLATOR1") (pin "13") (pinfunction "B1_13") (pintype "bidirectional"))
      (node (ref "ULTRA1") (pin "2") (pinfunction "2_2") (pintype "passive"))
    )
    (net (code "63") (name "/P8.1") (class "Default")
      (node (ref "LEVEL_TRANSLATOR1") (pin "3") (pinfunction "A2_3") (pintype "bidirectional"))
      (node (ref "MSP432P401R") (pin "31") (pinfunction "P8.1/UCB3CLK/TA2.0/C0.0_31") (pintype "power_in"))
    )
    (net (code "64") (name "/P8.1_5V") (class "Default")
      (node (ref "LEVEL_TRANSLATOR1") (pin "12") (pinfunction "B2_12") (pintype "bidirectional"))
      (node (ref "ULTRA1") (pin "3") (pinfunction "3_3") (pintype "passive"))
    )
    (net (code "65") (name "/P8.2") (class "Default")
      (node (ref "LEVEL_TRANSLATOR1") (pin "4") (pinfunction "A3_4") (pintype "bidirectional"))
      (node (ref "MSP432P401R") (pin "46") (pinfunction "P8.2/TA3.2/A23_46") (pintype "power_in"))
    )
    (net (code "66") (name "/P8.2_5V") (class "Default")
      (node (ref "LEVEL_TRANSLATOR1") (pin "11") (pinfunction "B3_11") (pintype "bidirectional"))
      (node (ref "ULTRA2") (pin "2") (pinfunction "2_2") (pintype "passive"))
    )
    (net (code "67") (name "/P8.5{slash}A20") (class "Default")
      (node (ref "MSP432P401R") (pin "49") (pinfunction "P8.5/A20_49") (pintype "power_in"))
    )
    (net (code "68") (name "/P8.6{slash}A19") (class "Default")
      (node (ref "MSP432P401R") (pin "50") (pinfunction "P8.6/A19_50") (pintype "power_in"))
    )
    (net (code "69") (name "/P8.7{slash}A18") (class "Default")
      (node (ref "MSP432P401R") (pin "51") (pinfunction "P8.7/A18_51") (pintype "power_in"))
    )
    (net (code "70") (name "/P9.0{slash}A17") (class "Default")
      (node (ref "MSP432P401R") (pin "52") (pinfunction "P9.0/A17_52") (pintype "power_in"))
    )
    (net (code "71") (name "/P9.1{slash}A16") (class "Default")
      (node (ref "MSP432P401R") (pin "53") (pinfunction "P9.1/A16_53") (pintype "power_in"))
    )
    (net (code "72") (name "/P9.2") (class "Default")
      (node (ref "LEVEL_TRANSLATOR1") (pin "5") (pinfunction "A4_5") (pintype "bidirectional"))
      (node (ref "MSP432P401R") (pin "74") (pinfunction "P9.2/TA3.3_74") (pintype "power_in"))
    )
    (net (code "73") (name "/P9.2_5V") (class "Default")
      (node (ref "LEVEL_TRANSLATOR1") (pin "10") (pinfunction "B4_10") (pintype "bidirectional"))
      (node (ref "ULTRA2") (pin "3") (pinfunction "3_3") (pintype "passive"))
    )
    (net (code "74") (name "/P9.3") (class "Default")
      (node (ref "LEVEL_TRANSLATOR_2") (pin "2") (pinfunction "A1_2") (pintype "bidirectional"))
      (node (ref "MSP432P401R") (pin "75") (pinfunction "P9.3/TA3.4_75") (pintype "power_in"))
    )
    (net (code "75") (name "/P9.3_5V") (class "Default")
      (node (ref "LEVEL_TRANSLATOR_2") (pin "13") (pinfunction "B1_13") (pintype "bidirectional"))
      (node (ref "ULTRA3") (pin "2") (pinfunction "2_2") (pintype "passive"))
    )
    (net (code "76") (name "/P9.4{slash}UCA3STE") (class "Default")
      (node (ref "MSP432P401R") (pin "96") (pinfunction "P9.4/UCA3STE_96") (pintype "power_in"))
    )
    (net (code "77") (name "/P9.5{slash}UCA3CLK") (class "Default")
      (node (ref "MSP432P401R") (pin "97") (pinfunction "P9.5/UCA3CLK_97") (pintype "power_in"))
    )
    (net (code "78") (name "/P9.6{slash}UCA3RXD{slash}UCA3SOMI") (class "Default")
      (node (ref "MSP432P401R") (pin "98") (pinfunction "P9.6/UCA3RXD/UCA3SOMI_98") (pintype "power_in"))
    )
    (net (code "79") (name "/P9.7{slash}UCA3TXD{slash}UCA3SIMO") (class "Default")
      (node (ref "MSP432P401R") (pin "99") (pinfunction "P9.7/UCA3TXD/UCA3SIMO_99") (pintype "power_in"))
    )
    (net (code "80") (name "/P10.0{slash}UCB3STE") (class "Default")
      (node (ref "MSP432P401R") (pin "100") (pinfunction "P10.0/UCB3STE_100") (pintype "power_in"))
    )
    (net (code "81") (name "/P10.1{slash}UCB3CLK") (class "Default")
      (node (ref "MSP432P401R") (pin "1") (pinfunction "P10.1/UCB3CLK_1") (pintype "power_in"))
    )
    (net (code "82") (name "/P10.2{slash}UCB3SIMO{slash}UCB3SDA") (class "Default")
      (node (ref "MSP432P401R") (pin "2") (pinfunction "P10.2/UCB3SIMO/UCB3SDA_2") (pintype "power_in"))
    )
    (net (code "83") (name "/P10.3") (class "Default")
      (node (ref "LEVEL_TRANSLATOR_2") (pin "5") (pinfunction "A4_5") (pintype "bidirectional"))
      (node (ref "MSP432P401R") (pin "3") (pinfunction "P10.3UCB3SOMI/UCB3SCL_3") (pintype "power_in"))
    )
    (net (code "84") (name "/P10.3_GPIO5V") (class "Default")
      (node (ref "LEVEL_TRANSLATOR_2") (pin "10") (pinfunction "B4_10") (pintype "bidirectional"))
      (node (ref "ULTRA4") (pin "3") (pinfunction "3_3") (pintype "passive"))
    )
    (net (code "85") (name "/P10.4") (class "Default")
      (node (ref "LEVEL_TRANSLATOR_2") (pin "3") (pinfunction "A2_3") (pintype "bidirectional"))
      (node (ref "MSP432P401R") (pin "24") (pinfunction "P10.4/TA3.0/C0.7_24") (pintype "power_in"))
    )
    (net (code "86") (name "/P10.4_5V") (class "Default")
      (node (ref "LEVEL_TRANSLATOR_2") (pin "12") (pinfunction "B2_12") (pintype "bidirectional"))
      (node (ref "ULTRA3") (pin "3") (pinfunction "3_3") (pintype "passive"))
    )
    (net (code "87") (name "/P10.5") (class "Default")
      (node (ref "LEVEL_TRANSLATOR_2") (pin "4") (pinfunction "A3_4") (pintype "bidirectional"))
      (node (ref "MSP432P401R") (pin "25") (pinfunction "P10.5/TA3.1/C0.6_25") (pintype "power_in"))
    )
    (net (code "88") (name "/P10.5_5V") (class "Default")
      (node (ref "LEVEL_TRANSLATOR_2") (pin "11") (pinfunction "B3_11") (pintype "bidirectional"))
      (node (ref "ULTRA4") (pin "2") (pinfunction "2_2") (pintype "passive"))
    )
    (net (code "89") (name "/PJ.0{slash}LFXIN") (class "Default")
      (node (ref "MSP432P401R") (pin "41") (pinfunction "PJ.0/LFXIN_41") (pintype "power_in"))
    )
    (net (code "90") (name "/PJ.1{slash}LFXOUT") (class "Default")
      (node (ref "MSP432P401R") (pin "42") (pinfunction "PJ.1/LFXOUT_42") (pintype "power_in"))
    )
    (net (code "91") (name "/PJ.2{slash}HFXOUT") (class "Default")
      (node (ref "MSP432P401R") (pin "85") (pinfunction "PJ.2/HFXOUT_85") (pintype "power_in"))
    )
    (net (code "92") (name "/PJ.3{slash}HFXIN") (class "Default")
      (node (ref "MSP432P401R") (pin "86") (pinfunction "PJ.3/HFXIN_86") (pintype "power_in"))
    )
    (net (code "93") (name "/VCORE") (class "Default")
      (node (ref "C11") (pin "1") (pinfunction "1_1") (pintype "passive"))
      (node (ref "CPOLARIZED") (pin "1") (pinfunction "1_1") (pintype "passive"))
      (node (ref "L1") (pin "1") (pinfunction "1_1") (pintype "passive"))
      (node (ref "MSP432P401R") (pin "12") (pinfunction "VCORE_12") (pintype "power_in"))
    )
    (net (code "94") (name "/VSW") (class "Default")
      (node (ref "L1") (pin "2") (pinfunction "2_2") (pintype "passive"))
      (node (ref "MSP432P401R") (pin "14") (pinfunction "VSW_14") (pintype "power_in"))
    )
    (net (code "95") (name "3.3V") (class "Default")
      (node (ref "LEVEL_TRANSLATOR1") (pin "1") (pinfunction "VCCA_1") (pintype "bidirectional"))
      (node (ref "LEVEL_TRANSLATOR1") (pin "8") (pinfunction "OE_8") (pintype "bidirectional"))
      (node (ref "LEVEL_TRANSLATOR_2") (pin "1") (pinfunction "VCCA_1") (pintype "bidirectional"))
      (node (ref "LEVEL_TRANSLATOR_2") (pin "8") (pinfunction "OE_8") (pintype "bidirectional"))
      (node (ref "LEVEL_TRANSLATOR_3") (pin "1") (pinfunction "VCCA_1") (pintype "bidirectional"))
      (node (ref "LEVEL_TRANSLATOR_3") (pin "8") (pinfunction "OE_8") (pintype "bidirectional"))
      (node (ref "R4") (pin "2") (pinfunction "2_2") (pintype "passive"))
      (node (ref "R5") (pin "2") (pinfunction "2_2") (pintype "passive"))
      (node (ref "R6") (pin "2") (pinfunction "2_2") (pintype "passive"))
    )
    (net (code "96") (name "3V3") (class "Default")
      (node (ref "BATTERY_FC_PINS") (pin "3") (pinfunction "3_3") (pintype "passive"))
      (node (ref "C2") (pin "1") (pinfunction "1_1") (pintype "passive"))
      (node (ref "C7") (pin "1") (pinfunction "1_1") (pintype "passive"))
      (node (ref "C8") (pin "1") (pinfunction "1_1") (pintype "passive"))
      (node (ref "CPOL") (pin "+") (pinfunction "+_+") (pintype "passive"))
      (node (ref "MSP432P401R") (pin "13") (pinfunction "DVCC1_13") (pintype "power_in"))
      (node (ref "MSP432P401R") (pin "73") (pinfunction "DVCC2_73") (pintype "power_in"))
      (node (ref "R2") (pin "2") (pinfunction "2_2") (pintype "passive"))
      (node (ref "R3") (pin "1") (pinfunction "1_1") (pintype "passive"))
      (node (ref "R8") (pin "1") (pinfunction "1_1") (pintype "passive"))
      (node (ref "TP3") (pin "TP") (pinfunction "TP_TP") (pintype "input"))
      (node (ref "U$1") (pin "3") (pinfunction "P$3_3") (pintype "bidirectional"))
      (node (ref "U$2") (pin "5") (pinfunction "OUT_5_5") (pintype "bidirectional"))
      (node (ref "U$3") (pin "3") (pinfunction "P$3_3") (pintype "bidirectional"))
    )
    (net (code "97") (name "5VDC") (class "Default")
      (node (ref "5V_PDB") (pin "1") (pinfunction "1_1") (pintype "passive"))
      (node (ref "C1") (pin "1") (pinfunction "1_1") (pintype "passive"))
      (node (ref "LEVEL_TRANSLATOR1") (pin "14") (pinfunction "VCCB_14") (pintype "bidirectional"))
      (node (ref "LEVEL_TRANSLATOR_2") (pin "14") (pinfunction "VCCB_14") (pintype "bidirectional"))
      (node (ref "LEVEL_TRANSLATOR_3") (pin "14") (pinfunction "VCCB_14") (pintype "bidirectional"))
      (node (ref "NAZE32_PINHEAD") (pin "2") (pinfunction "2_2") (pintype "passive"))
      (node (ref "R1") (pin "1") (pinfunction "1_1") (pintype "passive"))
      (node (ref "R7") (pin "1") (pinfunction "1_1") (pintype "passive"))
      (node (ref "U$1") (pin "6") (pinfunction "P$6_6") (pintype "bidirectional"))
      (node (ref "U$1") (pin "7") (pinfunction "P$7_7") (pintype "bidirectional"))
      (node (ref "U$2") (pin "1") (pinfunction "IN_1_1") (pintype "bidirectional"))
      (node (ref "U$2") (pin "3") (pinfunction "EN_3_3") (pintype "bidirectional"))
      (node (ref "U$3") (pin "6") (pinfunction "P$6_6") (pintype "bidirectional"))
      (node (ref "U$3") (pin "7") (pinfunction "P$7_7") (pintype "bidirectional"))
      (node (ref "ULTRA1") (pin "1") (pinfunction "1_1") (pintype "passive"))
      (node (ref "ULTRA2") (pin "1") (pinfunction "1_1") (pintype "passive"))
      (node (ref "ULTRA3") (pin "1") (pinfunction "1_1") (pintype "passive"))
      (node (ref "ULTRA4") (pin "1") (pinfunction "1_1") (pintype "passive"))
      (node (ref "ULTRA5") (pin "1") (pinfunction "1_1") (pintype "passive"))
      (node (ref "ULTRA6") (pin "1") (pinfunction "1_1") (pintype "passive"))
    )
    (net (code "98") (name "GND") (class "Default")
      (node (ref "5V_PDB") (pin "2") (pinfunction "2_2") (pintype "passive"))
      (node (ref "BATTERY_FC_PINS") (pin "2") (pinfunction "2_2") (pintype "passive"))
      (node (ref "BATTERY_FC_PINS") (pin "4") (pinfunction "4_4") (pintype "passive"))
      (node (ref "C1") (pin "2") (pinfunction "2_2") (pintype "passive"))
      (node (ref "C11") (pin "2") (pinfunction "2_2") (pintype "passive"))
      (node (ref "C13") (pin "2") (pinfunction "2_2") (pintype "passive"))
      (node (ref "C2") (pin "2") (pinfunction "2_2") (pintype "passive"))
      (node (ref "C3") (pin "2") (pinfunction "2_2") (pintype "passive"))
      (node (ref "C4") (pin "2") (pinfunction "2_2") (pintype "passive"))
      (node (ref "C7") (pin "2") (pinfunction "2_2") (pintype "passive"))
      (node (ref "C8") (pin "2") (pinfunction "2_2") (pintype "passive"))
      (node (ref "CPOL") (pin "-") (pinfunction "-_-") (pintype "passive"))
      (node (ref "CPOLARIZED") (pin "2") (pinfunction "2_2") (pintype "passive"))
      (node (ref "JTAG_DEBUG") (pin "3") (pinfunction "3_3") (pintype "passive"))
      (node (ref "JTAG_DEBUG") (pin "5") (pinfunction "5_5") (pintype "passive"))
      (node (ref "JTAG_DEBUG") (pin "7") (pinfunction "7_7") (pintype "passive"))
      (node (ref "JTAG_DEBUG") (pin "9") (pinfunction "9_9") (pintype "passive"))
      (node (ref "LED2") (pin "C") (pinfunction "C_C") (pintype "passive"))
      (node (ref "LEVEL_TRANSLATOR1") (pin "7") (pinfunction "GND_7") (pintype "bidirectional"))
      (node (ref "LEVEL_TRANSLATOR_2") (pin "7") (pinfunction "GND_7") (pintype "bidirectional"))
      (node (ref "LEVEL_TRANSLATOR_3") (pin "7") (pinfunction "GND_7") (pintype "bidirectional"))
      (node (ref "MSP432P401R") (pin "15") (pinfunction "DVSS1_15") (pintype "power_in"))
      (node (ref "MSP432P401R") (pin "40") (pinfunction "AVSS3_40") (pintype "power_in"))
      (node (ref "MSP432P401R") (pin "43") (pinfunction "AVSS1_43") (pintype "power_in"))
      (node (ref "MSP432P401R") (pin "72") (pinfunction "DVSS2_72") (pintype "power_in"))
      (node (ref "MSP432P401R") (pin "82") (pinfunction "DVSS3_82") (pintype "power_in"))
      (node (ref "MSP432P401R") (pin "84") (pinfunction "AVSS2_84") (pintype "power_in"))
      (node (ref "NAZE32_PINHEAD") (pin "1") (pinfunction "1_1") (pintype "passive"))
      (node (ref "POWER_LED") (pin "C") (pinfunction "C_C") (pintype "passive"))
      (node (ref "R1") (pin "2") (pinfunction "2_2") (pintype "passive"))
      (node (ref "R4") (pin "1") (pinfunction "1_1") (pintype "passive"))
      (node (ref "R5") (pin "1") (pinfunction "1_1") (pintype "passive"))
      (node (ref "R6") (pin "1") (pinfunction "1_1") (pintype "passive"))
      (node (ref "R7") (pin "2") (pinfunction "2_2") (pintype "passive"))
      (node (ref "TP2") (pin "TP") (pinfunction "TP_TP") (pintype "input"))
      (node (ref "U$1") (pin "2") (pinfunction "P$2_2") (pintype "bidirectional"))
      (node (ref "U$2") (pin "2") (pinfunction "GND_2_2") (pintype "bidirectional"))
      (node (ref "U$3") (pin "2") (pinfunction "P$2_2") (pintype "bidirectional"))
      (node (ref "U$4") (pin "1") (pinfunction "1_1") (pintype "passive"))
      (node (ref "U$4") (pin "2") (pinfunction "2_2") (pintype "passive"))
      (node (ref "ULTRA1") (pin "4") (pinfunction "4_4") (pintype "passive"))
      (node (ref "ULTRA2") (pin "4") (pinfunction "4_4") (pintype "passive"))
      (node (ref "ULTRA3") (pin "4") (pinfunction "4_4") (pintype "passive"))
      (node (ref "ULTRA4") (pin "4") (pinfunction "4_4") (pintype "passive"))
      (node (ref "ULTRA5") (pin "4") (pinfunction "4_4") (pintype "passive"))
      (node (ref "ULTRA6") (pin "4") (pinfunction "4_4") (pintype "passive"))
    )
    (net (code "99") (name "Net-(JTAG_DEBUG-Pad1)") (class "Default")
      (node (ref "JTAG_DEBUG") (pin "1") (pinfunction "1_1") (pintype "passive"))
      (node (ref "R8") (pin "2") (pinfunction "2_2") (pintype "passive"))
    )
    (net (code "100") (name "Net-(LED2-PadA)") (class "Default")
      (node (ref "LED2") (pin "A") (pinfunction "A_A") (pintype "passive"))
      (node (ref "R10") (pin "1") (pinfunction "1_1") (pintype "passive"))
    )
    (net (code "101") (name "Net-(MSP432P401R-AVCC1)") (class "Default")
      (node (ref "C3") (pin "1") (pinfunction "1_1") (pintype "passive"))
      (node (ref "C4") (pin "1") (pinfunction "1_1") (pintype "passive"))
      (node (ref "MSP432P401R") (pin "45") (pinfunction "AVCC1_45") (pintype "power_in"))
      (node (ref "MSP432P401R") (pin "87") (pinfunction "AVCC2_87") (pintype "power_in"))
      (node (ref "R3") (pin "2") (pinfunction "2_2") (pintype "passive"))
    )
    (net (code "102") (name "Net-(POWER_LED-PadA)") (class "Default")
      (node (ref "POWER_LED") (pin "A") (pinfunction "A_A") (pintype "passive"))
      (node (ref "R9") (pin "1") (pinfunction "1_1") (pintype "passive"))
    )
    (net (code "103") (name "P2.2_RX") (class "Default")
      (node (ref "MSP432P401R") (pin "18") (pinfunction "P2.2/PM_UCA1RXD/PM_UCA1SOMI_18") (pintype "power_in"))
      (node (ref "U$3") (pin "4") (pinfunction "P$4_4") (pintype "bidirectional"))
    )
    (net (code "104") (name "P2.7_PWM_J4.40") (class "Default")
      (node (ref "MSP432P401R") (pin "23") (pinfunction "P2.7/PM_TA0.4_23") (pintype "power_in"))
      (node (ref "NAZE32_PINHEAD") (pin "7") (pinfunction "7_7") (pintype "passive"))
    )
    (net (code "105") (name "P3.6_SDA") (class "Default")
      (node (ref "MSP432P401R") (pin "38") (pinfunction "P3.6/PM_UCB2SIMO/PM_UCB2SDA_38") (pintype "power_in"))
    )
    (net (code "106") (name "P3.7_SCL") (class "Default")
      (node (ref "MSP432P401R") (pin "39") (pinfunction "P3.7/PM_UCB2SOMI/PM_UCB2SCL_39") (pintype "power_in"))
    )
    (net (code "107") (name "P4.0_GPIO") (class "Default")
      (node (ref "GPIO_EXTRA") (pin "1") (pinfunction "1_1") (pintype "passive"))
      (node (ref "MSP432P401R") (pin "56") (pinfunction "P4.0/A13_56") (pintype "power_in"))
    )
    (net (code "108") (name "P4.1_GPIO") (class "Default")
      (node (ref "GPIO_EXTRA") (pin "2") (pinfunction "2_2") (pintype "passive"))
      (node (ref "MSP432P401R") (pin "57") (pinfunction "P4.1/A12_57") (pintype "power_in"))
    )
    (net (code "109") (name "P4.5_GPIO") (class "Default")
      (node (ref "GPIO_EXTRA") (pin "3") (pinfunction "3_3") (pintype "passive"))
      (node (ref "MSP432P401R") (pin "61") (pinfunction "P4.5/A8_61") (pintype "power_in"))
    )
    (net (code "110") (name "P4.6_GPIO") (class "Default")
      (node (ref "GPIO_EXTRA") (pin "4") (pinfunction "4_4") (pintype "passive"))
      (node (ref "MSP432P401R") (pin "62") (pinfunction "P4.6/A7_62") (pintype "power_in"))
    )
    (net (code "111") (name "P4.7_GPIO") (class "Default")
      (node (ref "GPIO_EXTRA") (pin "5") (pinfunction "5_5") (pintype "passive"))
      (node (ref "MSP432P401R") (pin "63") (pinfunction "P4.7/A6_63") (pintype "power_in"))
    )
    (net (code "112") (name "VBAT_TX") (class "Default")
      (node (ref "BATTERY_FC_PINS") (pin "1") (pinfunction "1_1") (pintype "passive"))
      (node (ref "U$3") (pin "5") (pinfunction "P$5_5") (pintype "bidirectional"))
    )
    (net (code "113") (name "unconnected-(MSP432P401R-P7.3{slash}PM_TA0.0-Pad91)") (class "Default")
      (node (ref "MSP432P401R") (pin "91") (pinfunction "P7.3/PM_TA0.0_91") (pintype "power_in"))
    )
    (net (code "114") (name "unconnected-(U$2-NC_4-Pad4)") (class "Default")
      (node (ref "U$2") (pin "4") (pinfunction "NC_4_4") (pintype "bidirectional"))
    )
    (net (code "115") (name "unconnected-(U$3-P$1-Pad1)") (class "Default")
      (node (ref "U$3") (pin "1") (pinfunction "P$1_1") (pintype "bidirectional"))
    )
    (net (code "116") (name "unconnected-(U$3-P$8-Pad8)") (class "Default")
      (node (ref "U$3") (pin "8") (pinfunction "P$8_8") (pintype "bidirectional"))
    )
  )
)
